# TFTBackpack.net
KiCad netlist of a schematic drawn in EAGLE
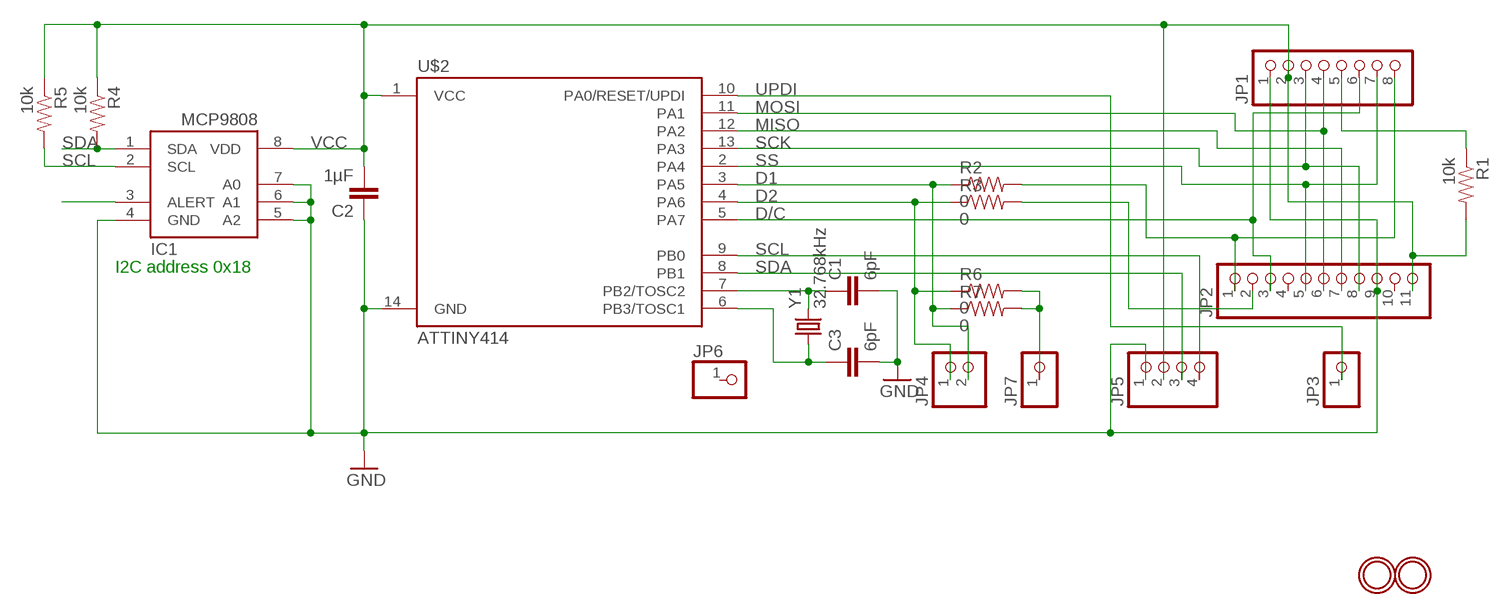
[diagram p0: schematic, sheet 1]

(export (version "E")
  (design (tool "Eeschema 10.0.6"))
  (components
    (comp (ref "C1")
      (value "6pF")
      (footprint "eagle-import:0805")
      (libsource (lib "eagle-import") (part "CAP0805"))
    )
    (comp (ref "C2")
      (value "1µF")
      (footprint "eagle-import:0805")
      (libsource (lib "eagle-import") (part "CAP0805"))
    )
    (comp (ref "C3")
      (value "6pF")
      (footprint "eagle-import:0805")
      (libsource (lib "eagle-import") (part "CAP0805"))
    )
    (comp (ref "IC1")
      (value "MCP9808-E/MS")
      (footprint "eagle-import:MSOP8_0.65MM")
      (libsource (lib "eagle-import") (part "MCP9808-E/MS"))
    )
    (comp (ref "JP1")
      (value "HEADER-1X8ROUND")
      (footprint "eagle-import:1X08_ROUND")
      (libsource (lib "eagle-import") (part "HEADER-1X8ROUND"))
    )
    (comp (ref "JP2")
      (value "HEADER-1X11")
      (footprint "eagle-import:1X11_ROUND")
      (libsource (lib "eagle-import") (part "HEADER-1X11"))
    )
    (comp (ref "JP3")
      (value "HEADER-1X1ROUND")
      (footprint "eagle-import:1X01_ROUND")
      (libsource (lib "eagle-import") (part "HEADER-1X1ROUND"))
    )
    (comp (ref "JP4")
      (value "HEADER-1X2ROUND")
      (footprint "eagle-import:1X02_ROUND")
      (libsource (lib "eagle-import") (part "HEADER-1X2ROUND"))
    )
    (comp (ref "JP5")
      (value "HEADER-1X4ROUND")
      (footprint "eagle-import:1X04_ROUND")
      (libsource (lib "eagle-import") (part "HEADER-1X4ROUND"))
    )
    (comp (ref "JP6")
      (value "HEADER-1X1ROUND")
      (footprint "eagle-import:1X01_ROUND")
      (libsource (lib "eagle-import") (part "HEADER-1X1ROUND"))
    )
    (comp (ref "JP7")
      (value "HEADER-1X1ROUND")
      (footprint "eagle-import:1X01_ROUND")
      (libsource (lib "eagle-import") (part "HEADER-1X1ROUND"))
    )
    (comp (ref "R1")
      (value "10k")
      (footprint "eagle-import:0805")
      (libsource (lib "eagle-import") (part "0.3OHM-1/8W-1%(0805)"))
    )
    (comp (ref "R2")
      (value "0")
      (footprint "eagle-import:0805")
      (libsource (lib "eagle-import") (part "0.3OHM-1/8W-1%(0805)"))
    )
    (comp (ref "R3")
      (value "0")
      (footprint "eagle-import:0805")
      (libsource (lib "eagle-import") (part "0.3OHM-1/8W-1%(0805)"))
    )
    (comp (ref "R4")
      (value "10k")
      (footprint "eagle-import:0805")
      (libsource (lib "eagle-import") (part "0.3OHM-1/8W-1%(0805)"))
    )
    (comp (ref "R5")
      (value "10k")
      (footprint "eagle-import:0805")
      (libsource (lib "eagle-import") (part "0.3OHM-1/8W-1%(0805)"))
    )
    (comp (ref "R6")
      (value "0")
      (footprint "eagle-import:0805")
      (libsource (lib "eagle-import") (part "0.3OHM-1/8W-1%(0805)"))
    )
    (comp (ref "R7")
      (value "0")
      (footprint "eagle-import:0805")
      (libsource (lib "eagle-import") (part "0.3OHM-1/8W-1%(0805)"))
    )
    (comp (ref "U$1")
      (value "MOUNTINGHOLE2.5")
      (footprint "eagle-import:MOUNTINGHOLE_2.5_PLATED")
      (libsource (lib "eagle-import") (part "MOUNTINGHOLE2.5"))
    )
    (comp (ref "U$2")
      (value "ATTINY414")
      (footprint "eagle-import:SO14")
      (libsource (lib "eagle-import") (part "ATTINY414"))
    )
    (comp (ref "U$9")
      (value "MOUNTINGHOLE2.5")
      (footprint "eagle-import:MOUNTINGHOLE_2.5_PLATED")
      (libsource (lib "eagle-import") (part "MOUNTINGHOLE2.5"))
    )
    (comp (ref "Y1")
      (value "32.768kHz")
      (footprint "eagle-import:CRYSTAL-SMD-3.2X1.5MM")
      (libsource (lib "eagle-import") (part "CRYSTAL3.2X1.5MM"))
    )
  )
  (nets
    (net (code "1") (name "/D1") (class "Default")
      (node (ref "JP4") (pin "2") (pinfunction "2_2") (pintype "passive"))
      (node (ref "R2") (pin "1") (pinfunction "1_1") (pintype "passive"))
      (node (ref "R7") (pin "1") (pinfunction "1_1") (pintype "passive"))
      (node (ref "U$2") (pin "3") (pinfunction "PA5_3") (pintype "bidirectional"))
    )
    (net (code "2") (name "/D2") (class "Default")
      (node (ref "JP4") (pin "1") (pinfunction "1_1") (pintype "passive"))
      (node (ref "R3") (pin "1") (pinfunction "1_1") (pintype "passive"))
      (node (ref "R6") (pin "1") (pinfunction "1_1") (pintype "passive"))
      (node (ref "U$2") (pin "4") (pinfunction "PA6_4") (pintype "bidirectional"))
    )
    (net (code "3") (name "/D{slash}C") (class "Default")
      (node (ref "JP1") (pin "6") (pinfunction "6_6") (pintype "passive"))
      (node (ref "JP2") (pin "3") (pinfunction "3_3") (pintype "passive"))
      (node (ref "U$2") (pin "5") (pinfunction "PA7_5") (pintype "bidirectional"))
    )
    (net (code "4") (name "/MISO") (class "Default")
      (node (ref "JP2") (pin "7") (pinfunction "7_7") (pintype "passive"))
      (node (ref "U$2") (pin "12") (pinfunction "PA2_12") (pintype "bidirectional"))
    )
    (net (code "5") (name "/MOSI") (class "Default")
      (node (ref "JP1") (pin "4") (pinfunction "4_4") (pintype "passive"))
      (node (ref "JP2") (pin "6") (pinfunction "6_6") (pintype "passive"))
      (node (ref "U$2") (pin "11") (pinfunction "PA1_11") (pintype "bidirectional"))
    )
    (net (code "6") (name "/SCK") (class "Default")
      (node (ref "JP1") (pin "3") (pinfunction "3_3") (pintype "passive"))
      (node (ref "JP2") (pin "8") (pinfunction "8_8") (pintype "passive"))
      (node (ref "U$2") (pin "13") (pinfunction "PA3_13") (pintype "bidirectional"))
    )
    (net (code "7") (name "/SCL") (class "Default")
      (node (ref "IC1") (pin "2") (pinfunction "SCL_2") (pintype "bidirectional"))
      (node (ref "JP5") (pin "4") (pinfunction "4_4") (pintype "passive"))
      (node (ref "R5") (pin "2") (pinfunction "2_2") (pintype "passive"))
      (node (ref "U$2") (pin "9") (pinfunction "PB0_9") (pintype "bidirectional"))
    )
    (net (code "8") (name "/SDA") (class "Default")
      (node (ref "IC1") (pin "1") (pinfunction "SDA_1") (pintype "bidirectional"))
      (node (ref "JP5") (pin "3") (pinfunction "3_3") (pintype "passive"))
      (node (ref "R4") (pin "2") (pinfunction "2_2") (pintype "passive"))
      (node (ref "U$2") (pin "8") (pinfunction "PB1_8") (pintype "bidirectional"))
    )
    (net (code "9") (name "/SS") (class "Default")
      (node (ref "JP1") (pin "7") (pinfunction "7_7") (pintype "passive"))
      (node (ref "JP2") (pin "5") (pinfunction "5_5") (pintype "passive"))
      (node (ref "U$2") (pin "2") (pinfunction "PA4_2") (pintype "bidirectional"))
    )
    (net (code "10") (name "/UPDI") (class "Default")
      (node (ref "JP3") (pin "1") (pinfunction "1_1") (pintype "passive"))
      (node (ref "U$2") (pin "10") (pinfunction "PA0/RESET/UPDI_10") (pintype "bidirectional"))
    )
    (net (code "11") (name "/VCC") (class "Default")
      (node (ref "C2") (pin "2") (pinfunction "2_2") (pintype "passive"))
      (node (ref "IC1") (pin "8") (pinfunction "VDD_8") (pintype "power_in"))
      (node (ref "JP1") (pin "2") (pinfunction "2_2") (pintype "passive"))
      (node (ref "JP2") (pin "11") (pinfunction "11_11") (pintype "passive"))
      (node (ref "JP5") (pin "2") (pinfunction "2_2") (pintype "passive"))
      (node (ref "R1") (pin "2") (pinfunction "2_2") (pintype "passive"))
      (node (ref "R4") (pin "1") (pinfunction "1_1") (pintype "passive"))
      (node (ref "R5") (pin "1") (pinfunction "1_1") (pintype "passive"))
      (node (ref "U$2") (pin "1") (pinfunction "VCC_1") (pintype "bidirectional"))
    )
    (net (code "12") (name "GND") (class "Default")
      (node (ref "C1") (pin "2") (pinfunction "2_2") (pintype "passive"))
      (node (ref "C2") (pin "1") (pinfunction "1_1") (pintype "passive"))
      (node (ref "C3") (pin "2") (pinfunction "2_2") (pintype "passive"))
      (node (ref "IC1") (pin "4") (pinfunction "GND_4") (pintype "power_in"))
      (node (ref "IC1") (pin "5") (pinfunction "A2_5") (pintype "input"))
      (node (ref "IC1") (pin "6") (pinfunction "A1_6") (pintype "input"))
      (node (ref "IC1") (pin "7") (pinfunction "A0_7") (pintype "input"))
      (node (ref "JP1") (pin "1") (pinfunction "1_1") (pintype "passive"))
      (node (ref "JP2") (pin "9") (pinfunction "9_9") (pintype "passive"))
      (node (ref "JP5") (pin "1") (pinfunction "1_1") (pintype "passive"))
      (node (ref "U$2") (pin "14") (pinfunction "GND_14") (pintype "bidirectional"))
    )
    (net (code "13") (name "Net-(JP1-Pad5)") (class "Default")
      (node (ref "JP1") (pin "5") (pinfunction "5_5") (pintype "passive"))
      (node (ref "R1") (pin "1") (pinfunction "1_1") (pintype "passive"))
    )
    (net (code "14") (name "Net-(JP1-Pad8)") (class "Default")
      (node (ref "JP1") (pin "8") (pinfunction "8_8") (pintype "passive"))
      (node (ref "JP2") (pin "1") (pinfunction "1_1") (pintype "passive"))
      (node (ref "R2") (pin "2") (pinfunction "2_2") (pintype "passive"))
    )
    (net (code "15") (name "Net-(JP2-Pad2)") (class "Default")
      (node (ref "JP2") (pin "2") (pinfunction "2_2") (pintype "passive"))
      (node (ref "R3") (pin "2") (pinfunction "2_2") (pintype "passive"))
    )
    (net (code "16") (name "Net-(JP7-Pad1)") (class "Default")
      (node (ref "JP7") (pin "1") (pinfunction "1_1") (pintype "passive"))
      (node (ref "R6") (pin "2") (pinfunction "2_2") (pintype "passive"))
      (node (ref "R7") (pin "2") (pinfunction "2_2") (pintype "passive"))
    )
    (net (code "17") (name "Net-(U$2-PB2{slash}TOSC2)") (class "Default")
      (node (ref "C1") (pin "1") (pinfunction "1_1") (pintype "passive"))
      (node (ref "U$2") (pin "7") (pinfunction "PB2/TOSC2_7") (pintype "bidirectional"))
      (node (ref "Y1") (pin "P$2") (pinfunction "2_P$2") (pintype "passive"))
    )
    (net (code "18") (name "Net-(U$2-PB3{slash}TOSC1)") (class "Default")
      (node (ref "C3") (pin "1") (pinfunction "1_1") (pintype "passive"))
      (node (ref "U$2") (pin "6") (pinfunction "PB3/TOSC1_6") (pintype "bidirectional"))
      (node (ref "Y1") (pin "P$1") (pinfunction "1_P$1") (pintype "passive"))
    )
    (net (code "19") (name "unconnected-(IC1-ALERT-Pad3)") (class "Default")
      (node (ref "IC1") (pin "3") (pinfunction "ALERT_3") (pintype "open_collector"))
    )
    (net (code "20") (name "unconnected-(JP2-Pad4)") (class "Default")
      (node (ref "JP2") (pin "4") (pinfunction "4_4") (pintype "passive"))
    )
    (net (code "21") (name "unconnected-(JP2-Pad10)") (class "Default")
      (node (ref "JP2") (pin "10") (pinfunction "10_10") (pintype "passive"))
    )
    (net (code "22") (name "unconnected-(JP6-Pad1)") (class "Default")
      (node (ref "JP6") (pin "1") (pinfunction "1_1") (pintype "passive"))
    )
  )
)
